# CP2102_breakout.net
KiCad netlist of a schematic drawn in EAGLE
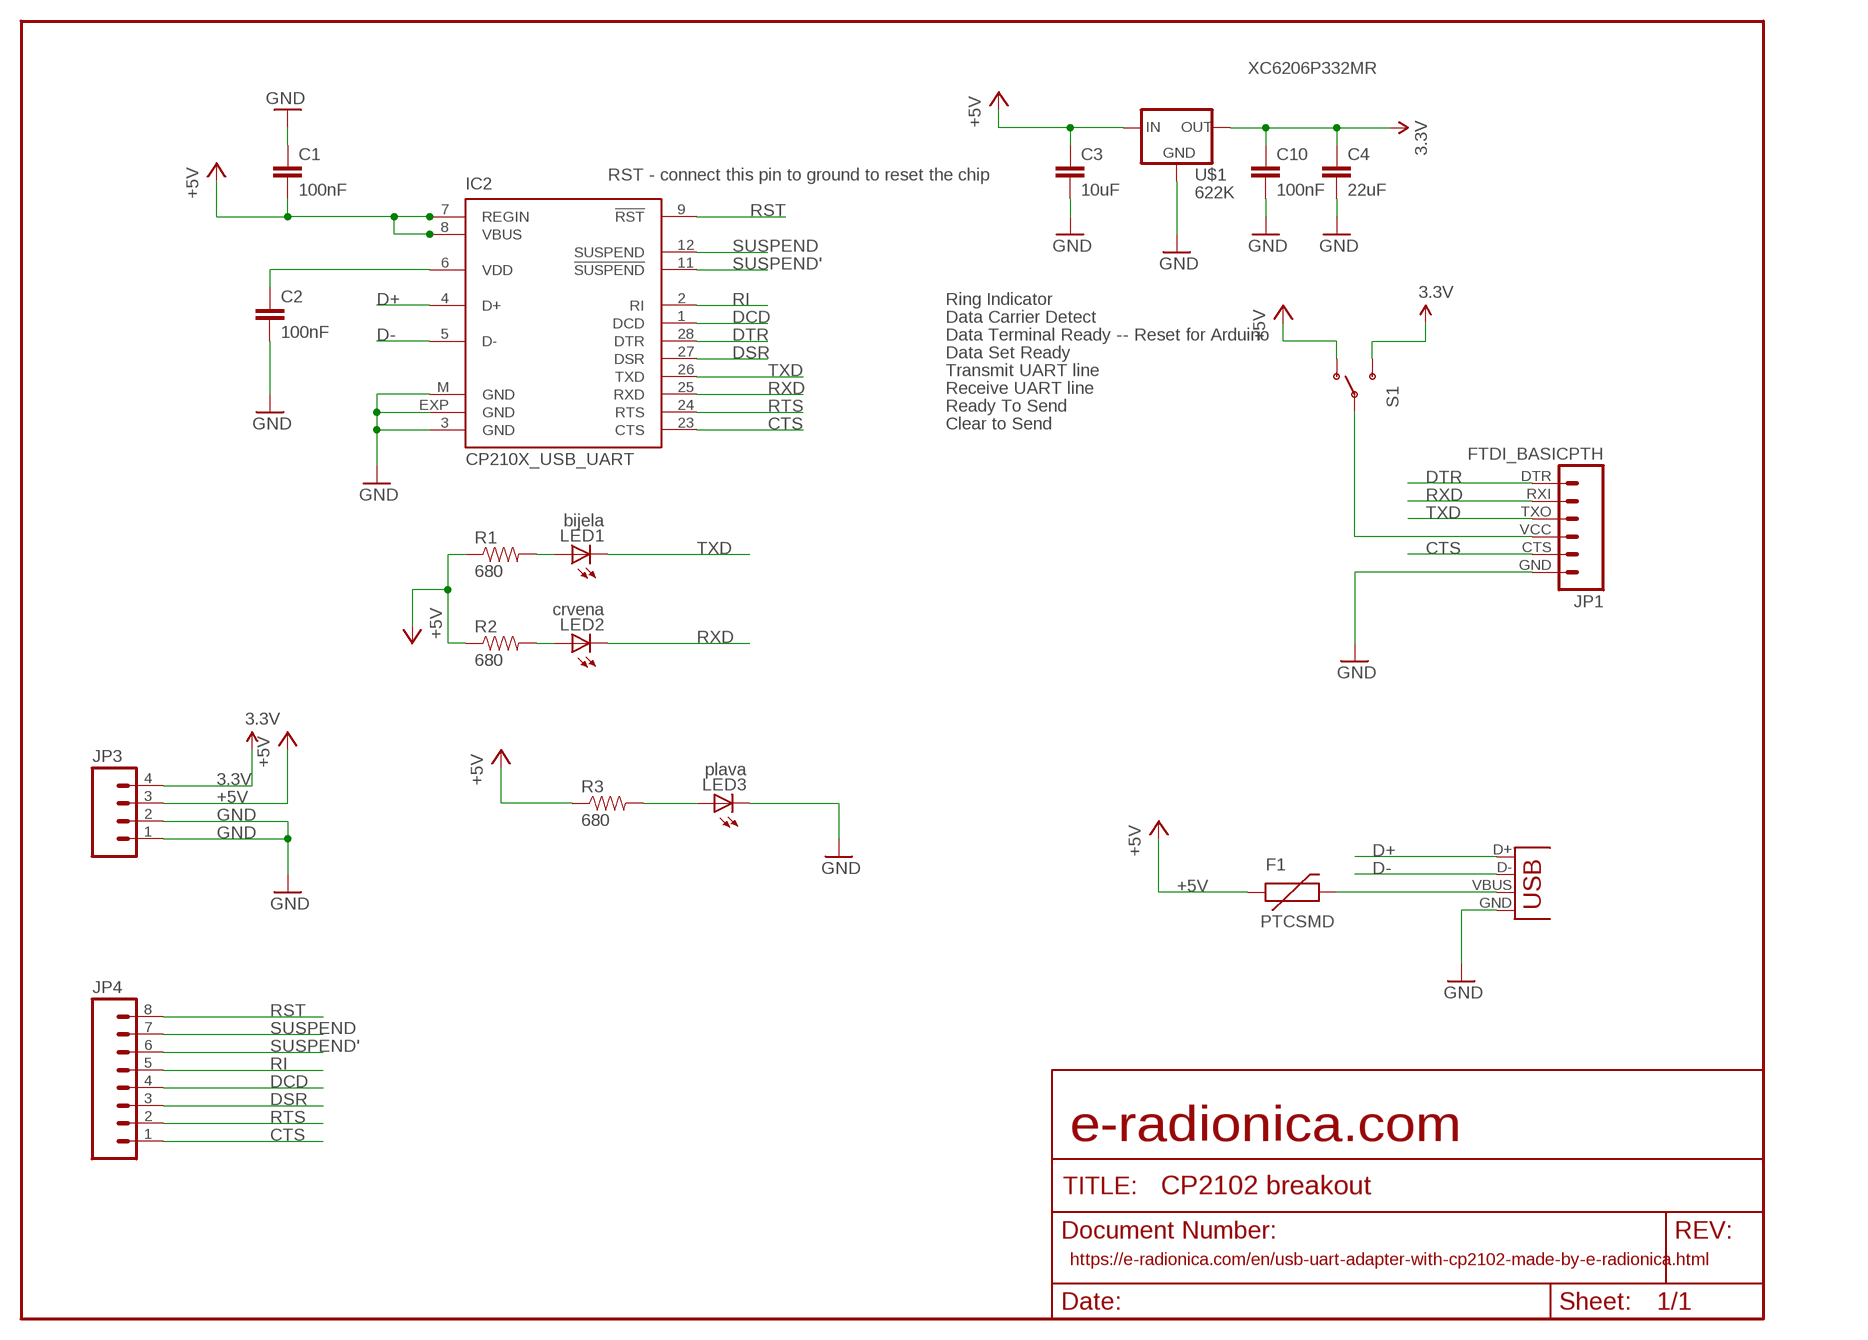
[diagram p0: schematic, sheet 1]

(export (version "E")
  (design (tool "Eeschema 10.0.6"))
  (components
    (comp (ref "C1")
      (value "100nF")
      (footprint "eagle-import:0603-CAP")
      (libsource (lib "eagle-import") (part "CAP0603-CAP"))
    )
    (comp (ref "C2")
      (value "100nF")
      (footprint "eagle-import:0603-CAP")
      (libsource (lib "eagle-import") (part "CAP0603-CAP"))
    )
    (comp (ref "C3")
      (value "10uF")
      (footprint "eagle-import:C3216")
      (libsource (lib "eagle-import") (part "C-EUC3216"))
    )
    (comp (ref "C4")
      (value "22uF")
      (footprint "eagle-import:C3216")
      (libsource (lib "eagle-import") (part "C-EUC3216"))
    )
    (comp (ref "C10")
      (value "100nF")
      (footprint "eagle-import:0603-CAP")
      (libsource (lib "eagle-import") (part "CAP0603-CAP"))
    )
    (comp (ref "F1")
      (value "PTCSMD")
      (footprint "eagle-import:PTC-1206")
      (libsource (lib "eagle-import") (part "PTCSMD"))
    )
    (comp (ref "IC2")
      (value "CP210X_USB_UART")
      (footprint "eagle-import:MLP28")
      (libsource (lib "eagle-import") (part "CP210X_USB_UART"))
    )
    (comp (ref "JP1")
      (value "FTDI_BASICPTH")
      (footprint "eagle-import:FTDI_BASIC")
      (libsource (lib "eagle-import") (part "FTDI_BASICPTH"))
    )
    (comp (ref "JP3")
      (value "M04PTH")
      (footprint "eagle-import:1X04")
      (libsource (lib "eagle-import") (part "M04PTH"))
    )
    (comp (ref "JP4")
      (value "M081X08")
      (footprint "eagle-import:1X08")
      (libsource (lib "eagle-import") (part "M081X08"))
    )
    (comp (ref "LED1")
      (value "bijela")
      (footprint "eagle-import:CHIP-LED0805")
      (libsource (lib "eagle-import") (part "LEDCHIP-LED0805"))
    )
    (comp (ref "LED2")
      (value "crvena")
      (footprint "eagle-import:CHIP-LED0805")
      (libsource (lib "eagle-import") (part "LEDCHIP-LED0805"))
    )
    (comp (ref "LED3")
      (value "plava")
      (footprint "eagle-import:CHIP-LED0805")
      (libsource (lib "eagle-import") (part "LEDCHIP-LED0805"))
    )
    (comp (ref "R1")
      (value "680")
      (footprint "eagle-import:0603-RES")
      (libsource (lib "eagle-import") (part "RESISTOR0603-RES"))
    )
    (comp (ref "R2")
      (value "680")
      (footprint "eagle-import:0603-RES")
      (libsource (lib "eagle-import") (part "RESISTOR0603-RES"))
    )
    (comp (ref "R3")
      (value "680")
      (footprint "eagle-import:0603-RES")
      (libsource (lib "eagle-import") (part "RESISTOR0603-RES"))
    )
    (comp (ref "S1")
      (value "SWITCH-SPST-SMD-A")
      (footprint "eagle-import:SWITCH-SPST-SMD-A")
      (libsource (lib "eagle-import") (part "SWITCH-SPST-SMD-A"))
    )
    (comp (ref "U$1")
      (value "622K")
      (footprint "eagle-import:662K")
      (libsource (lib "eagle-import") (part "622K"))
    )
    (comp (ref "X1")
      (value "USB-MICROB")
      (footprint "eagle-import:USB-MICROB")
      (libsource (lib "eagle-import") (part "USB-MICROB"))
    )
  )
  (nets
    (net (code "1") (name "+5V") (class "Default")
      (node (ref "C1") (pin "2") (pinfunction "2_2") (pintype "passive"))
      (node (ref "C3") (pin "1") (pinfunction "1_1") (pintype "passive"))
      (node (ref "F1") (pin "1") (pinfunction "1_1") (pintype "bidirectional"))
      (node (ref "IC2") (pin "7") (pinfunction "REGIN_7") (pintype "passive"))
      (node (ref "IC2") (pin "8") (pinfunction "VBUS_8") (pintype "input"))
      (node (ref "JP3") (pin "3") (pinfunction "3_3") (pintype "passive"))
      (node (ref "R1") (pin "1") (pinfunction "1_1") (pintype "passive"))
      (node (ref "R2") (pin "1") (pinfunction "1_1") (pintype "passive"))
      (node (ref "R3") (pin "1") (pinfunction "1_1") (pintype "passive"))
      (node (ref "S1") (pin "1") (pinfunction "O_1") (pintype "passive"))
      (node (ref "U$1") (pin "IN") (pinfunction "IN_IN") (pintype "input"))
    )
    (net (code "2") (name "/CTS") (class "Default")
      (node (ref "IC2") (pin "23") (pinfunction "CTS_23") (pintype "input"))
      (node (ref "JP1") (pin "CTS") (pinfunction "5_CTS") (pintype "passive"))
      (node (ref "JP4") (pin "1") (pinfunction "1_1") (pintype "passive"))
    )
    (net (code "3") (name "/D+") (class "Default")
      (node (ref "IC2") (pin "4") (pinfunction "D+_4") (pintype "bidirectional"))
      (node (ref "X1") (pin "D+") (pinfunction "D+_D+") (pintype "bidirectional"))
    )
    (net (code "4") (name "/D-") (class "Default")
      (node (ref "IC2") (pin "5") (pinfunction "D-_5") (pintype "bidirectional"))
      (node (ref "X1") (pin "D-") (pinfunction "D-_D-") (pintype "bidirectional"))
    )
    (net (code "5") (name "/DCD") (class "Default")
      (node (ref "IC2") (pin "1") (pinfunction "DCD_1") (pintype "input"))
      (node (ref "JP4") (pin "4") (pinfunction "4_4") (pintype "passive"))
    )
    (net (code "6") (name "/DSR") (class "Default")
      (node (ref "IC2") (pin "27") (pinfunction "DSR_27") (pintype "input"))
      (node (ref "JP4") (pin "3") (pinfunction "3_3") (pintype "passive"))
    )
    (net (code "7") (name "/DTR") (class "Default")
      (node (ref "IC2") (pin "28") (pinfunction "DTR_28") (pintype "output"))
      (node (ref "JP1") (pin "DTR") (pinfunction "1_DTR") (pintype "passive"))
    )
    (net (code "8") (name "/RI") (class "Default")
      (node (ref "IC2") (pin "2") (pinfunction "RI_2") (pintype "input"))
      (node (ref "JP4") (pin "5") (pinfunction "5_5") (pintype "passive"))
    )
    (net (code "9") (name "/RST") (class "Default")
      (node (ref "IC2") (pin "9") (pinfunction "~{RST}_9") (pintype "bidirectional"))
      (node (ref "JP4") (pin "8") (pinfunction "8_8") (pintype "passive"))
    )
    (net (code "10") (name "/RTS") (class "Default")
      (node (ref "IC2") (pin "24") (pinfunction "RTS_24") (pintype "output"))
      (node (ref "JP4") (pin "2") (pinfunction "2_2") (pintype "passive"))
    )
    (net (code "11") (name "/RXD") (class "Default")
      (node (ref "IC2") (pin "25") (pinfunction "RXD_25") (pintype "input"))
      (node (ref "JP1") (pin "RXI") (pinfunction "2_RXI") (pintype "passive"))
      (node (ref "LED2") (pin "C") (pinfunction "C_C") (pintype "passive"))
    )
    (net (code "12") (name "/SUSPEND") (class "Default")
      (node (ref "IC2") (pin "12") (pinfunction "SUSPEND_12") (pintype "output"))
      (node (ref "JP4") (pin "7") (pinfunction "7_7") (pintype "passive"))
    )
    (net (code "13") (name "/SUSPEND'") (class "Default")
      (node (ref "IC2") (pin "11") (pinfunction "~{SUSPEND}_11") (pintype "output"))
      (node (ref "JP4") (pin "6") (pinfunction "6_6") (pintype "passive"))
    )
    (net (code "14") (name "/TXD") (class "Default")
      (node (ref "IC2") (pin "26") (pinfunction "TXD_26") (pintype "output"))
      (node (ref "JP1") (pin "TXO") (pinfunction "3_TXO") (pintype "passive"))
      (node (ref "LED1") (pin "C") (pinfunction "C_C") (pintype "passive"))
    )
    (net (code "15") (name "3.3V") (class "Default")
      (node (ref "C10") (pin "1") (pinfunction "1_1") (pintype "passive"))
      (node (ref "C4") (pin "1") (pinfunction "1_1") (pintype "passive"))
      (node (ref "JP3") (pin "4") (pinfunction "4_4") (pintype "passive"))
      (node (ref "S1") (pin "3") (pinfunction "S_3") (pintype "passive"))
      (node (ref "U$1") (pin "OUT") (pinfunction "OUT_OUT") (pintype "output"))
    )
    (net (code "16") (name "GND") (class "Default")
      (node (ref "C1") (pin "1") (pinfunction "1_1") (pintype "passive"))
      (node (ref "C10") (pin "2") (pinfunction "2_2") (pintype "passive"))
      (node (ref "C2") (pin "2") (pinfunction "2_2") (pintype "passive"))
      (node (ref "C3") (pin "2") (pinfunction "2_2") (pintype "passive"))
      (node (ref "C4") (pin "2") (pinfunction "2_2") (pintype "passive"))
      (node (ref "IC2") (pin "3") (pinfunction "GND_3") (pintype "power_in"))
      (node (ref "IC2") (pin "EXP") (pinfunction "GND_EXP") (pintype "power_in"))
      (node (ref "IC2") (pin "M") (pinfunction "GND_M") (pintype "power_in"))
      (node (ref "JP1") (pin "GND") (pinfunction "6_GND") (pintype "passive"))
      (node (ref "JP3") (pin "1") (pinfunction "1_1") (pintype "passive"))
      (node (ref "JP3") (pin "2") (pinfunction "2_2") (pintype "passive"))
      (node (ref "LED3") (pin "C") (pinfunction "C_C") (pintype "passive"))
      (node (ref "U$1") (pin "GND") (pinfunction "GND_GND") (pintype "input"))
      (node (ref "X1") (pin "GND") (pinfunction "GND_GND") (pintype "bidirectional"))
    )
    (net (code "17") (name "Net-(F1-Pad2)") (class "Default")
      (node (ref "F1") (pin "2") (pinfunction "2_2") (pintype "bidirectional"))
      (node (ref "X1") (pin "VBUS") (pinfunction "VBUS_VBUS") (pintype "bidirectional"))
    )
    (net (code "18") (name "Net-(IC2-VDD)") (class "Default")
      (node (ref "C2") (pin "1") (pinfunction "1_1") (pintype "passive"))
      (node (ref "IC2") (pin "6") (pinfunction "VDD_6") (pintype "power_in"))
    )
    (net (code "19") (name "Net-(JP1-4)") (class "Default")
      (node (ref "JP1") (pin "VCC") (pinfunction "4_VCC") (pintype "passive"))
      (node (ref "S1") (pin "2") (pinfunction "P_2") (pintype "passive"))
    )
    (net (code "20") (name "Net-(LED1-PadA)") (class "Default")
      (node (ref "LED1") (pin "A") (pinfunction "A_A") (pintype "passive"))
      (node (ref "R1") (pin "2") (pinfunction "2_2") (pintype "passive"))
    )
    (net (code "21") (name "Net-(LED2-PadA)") (class "Default")
      (node (ref "LED2") (pin "A") (pinfunction "A_A") (pintype "passive"))
      (node (ref "R2") (pin "2") (pinfunction "2_2") (pintype "passive"))
    )
    (net (code "22") (name "Net-(LED3-PadA)") (class "Default")
      (node (ref "LED3") (pin "A") (pinfunction "A_A") (pintype "passive"))
      (node (ref "R3") (pin "2") (pinfunction "2_2") (pintype "passive"))
    )
  )
)
